# accuphase_e202_rectifier.net
KiCad netlist of a schematic drawn in EAGLE
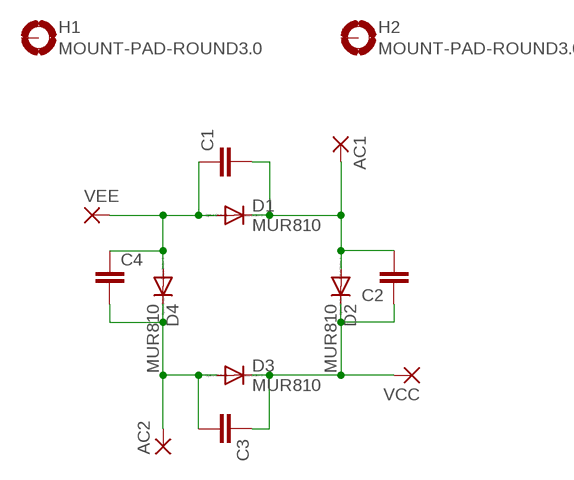
[diagram p0: schematic, sheet 1]

(export (version "E")
  (design (tool "Eeschema 10.0.6"))
  (components
    (comp (ref "AC1")
      (value "3,81/1,4")
      (footprint "eagle-import:3,81_1,4")
      (libsource (lib "eagle-import") (part "3,81/1,4"))
    )
    (comp (ref "AC2")
      (value "3,81/1,4")
      (footprint "eagle-import:3,81_1,4")
      (libsource (lib "eagle-import") (part "3,81/1,4"))
    )
    (comp (ref "C1")
      (value "C-EU075-032X103")
      (footprint "eagle-import:C075-032X103")
      (libsource (lib "eagle-import") (part "C-EU075-032X103"))
    )
    (comp (ref "C2")
      (value "C-EU075-032X103")
      (footprint "eagle-import:C075-032X103")
      (libsource (lib "eagle-import") (part "C-EU075-032X103"))
    )
    (comp (ref "C3")
      (value "C-EU075-032X103")
      (footprint "eagle-import:C075-032X103")
      (libsource (lib "eagle-import") (part "C-EU075-032X103"))
    )
    (comp (ref "C4")
      (value "C-EU075-032X103")
      (footprint "eagle-import:C075-032X103")
      (libsource (lib "eagle-import") (part "C-EU075-032X103"))
    )
    (comp (ref "D1")
      (value "MUR810")
      (footprint "eagle-import:TO220ACS")
      (libsource (lib "eagle-import") (part "MUR810"))
    )
    (comp (ref "D2")
      (value "MUR810")
      (footprint "eagle-import:TO220ACS")
      (libsource (lib "eagle-import") (part "MUR810"))
    )
    (comp (ref "D3")
      (value "MUR810")
      (footprint "eagle-import:TO220ACS")
      (libsource (lib "eagle-import") (part "MUR810"))
    )
    (comp (ref "D4")
      (value "MUR810")
      (footprint "eagle-import:TO220ACS")
      (libsource (lib "eagle-import") (part "MUR810"))
    )
    (comp (ref "H1")
      (value "MOUNT-PAD-ROUND3.0")
      (footprint "eagle-import:3,0-PAD")
      (libsource (lib "eagle-import") (part "MOUNT-PAD-ROUND3.0"))
    )
    (comp (ref "H2")
      (value "MOUNT-PAD-ROUND3.0")
      (footprint "eagle-import:3,0-PAD")
      (libsource (lib "eagle-import") (part "MOUNT-PAD-ROUND3.0"))
    )
    (comp (ref "VCC")
      (value "3,81/1,4")
      (footprint "eagle-import:3,81_1,4")
      (libsource (lib "eagle-import") (part "3,81/1,4"))
    )
    (comp (ref "VEE")
      (value "3,81/1,4")
      (footprint "eagle-import:3,81_1,4")
      (libsource (lib "eagle-import") (part "3,81/1,4"))
    )
  )
  (nets
    (net (code "1") (name "Net-(AC1-P)") (class "Default")
      (node (ref "AC1") (pin "1") (pinfunction "P_1") (pintype "passive"))
      (node (ref "C1") (pin "2") (pinfunction "2_2") (pintype "passive"))
      (node (ref "C2") (pin "2") (pinfunction "2_2") (pintype "passive"))
      (node (ref "D1") (pin "C") (pinfunction "C_C") (pintype "passive"))
      (node (ref "D2") (pin "A") (pinfunction "A_A") (pintype "passive"))
    )
    (net (code "2") (name "Net-(AC2-P)") (class "Default")
      (node (ref "AC2") (pin "1") (pinfunction "P_1") (pintype "passive"))
      (node (ref "C3") (pin "2") (pinfunction "2_2") (pintype "passive"))
      (node (ref "C4") (pin "2") (pinfunction "2_2") (pintype "passive"))
      (node (ref "D3") (pin "A") (pinfunction "A_A") (pintype "passive"))
      (node (ref "D4") (pin "C") (pinfunction "C_C") (pintype "passive"))
    )
    (net (code "3") (name "Net-(VCC-P)") (class "Default")
      (node (ref "C2") (pin "1") (pinfunction "1_1") (pintype "passive"))
      (node (ref "C3") (pin "1") (pinfunction "1_1") (pintype "passive"))
      (node (ref "D2") (pin "C") (pinfunction "C_C") (pintype "passive"))
      (node (ref "D3") (pin "C") (pinfunction "C_C") (pintype "passive"))
      (node (ref "VCC") (pin "1") (pinfunction "P_1") (pintype "passive"))
    )
    (net (code "4") (name "Net-(VEE-P)") (class "Default")
      (node (ref "C1") (pin "1") (pinfunction "1_1") (pintype "passive"))
      (node (ref "C4") (pin "1") (pinfunction "1_1") (pintype "passive"))
      (node (ref "D1") (pin "A") (pinfunction "A_A") (pintype "passive"))
      (node (ref "D4") (pin "A") (pinfunction "A_A") (pintype "passive"))
      (node (ref "VEE") (pin "1") (pinfunction "P_1") (pintype "passive"))
    )
    (net (code "5") (name "unconnected-(H1-MOUNT-PadB3,0)") (class "Default")
      (node (ref "H1") (pin "B3,0") (pinfunction "MOUNT_B3,0") (pintype "passive"))
    )
    (net (code "6") (name "unconnected-(H2-MOUNT-PadB3,0)") (class "Default")
      (node (ref "H2") (pin "B3,0") (pinfunction "MOUNT_B3,0") (pintype "passive"))
    )
  )
)
